# USB_HUB.net
KiCad netlist of a schematic drawn in Altium Designer
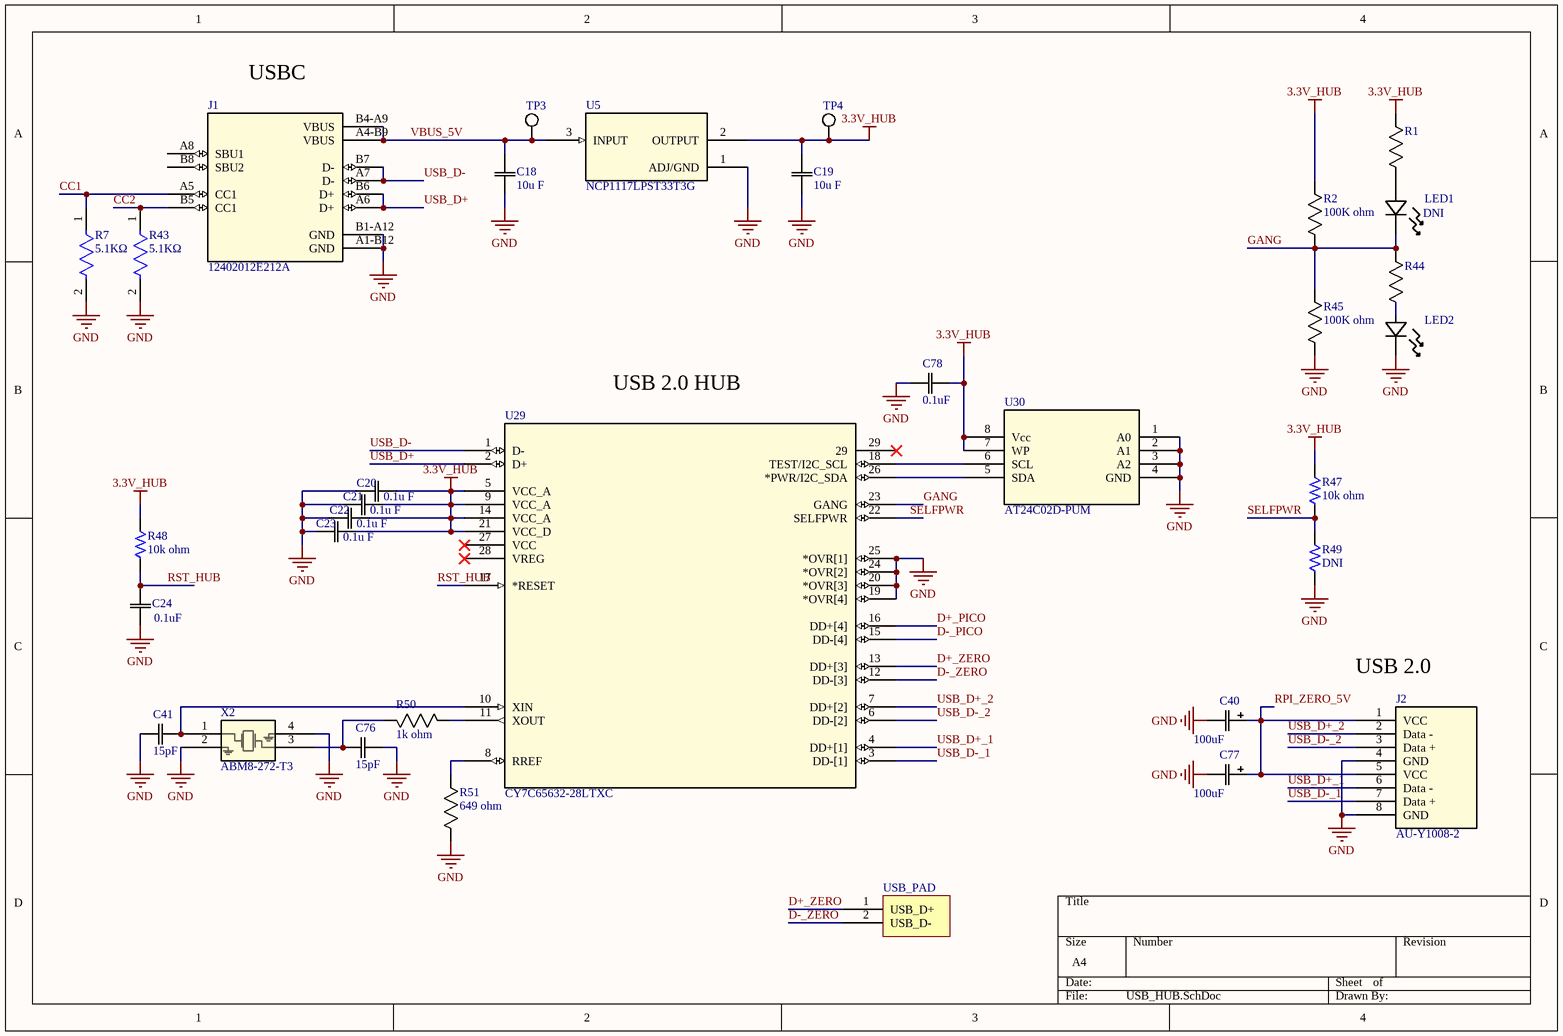
[diagram p0: USB_HUB.SchDoc]

(export (version "E")
  (design (tool "Eeschema 10.0.6"))
  (components
    (comp (ref "C18")
      (value "10u F")
      (footprint "G-21_MUR-M")
      (description "10 µF ±10% 16V Ceramic Capacitor X5R 0805 (2012 Metric)")
      (fields (field (name "Comment") "GRM21BR61C106KE15K"))
      (libsource (lib "Schlib1") (part "CAP_GRM21BR61C106KE15K"))
    )
    (comp (ref "C19")
      (value "10u F")
      (footprint "G-21_MUR-M")
      (description "10 µF ±10% 16V Ceramic Capacitor X5R 0805 (2012 Metric)")
      (fields (field (name "Comment") "GRM21BR61C106KE15K"))
      (libsource (lib "Schlib1") (part "CAP_GRM21BR61C106KE15K"))
    )
    (comp (ref "C20")
      (value "0.1u F")
      (footprint "CC0805N_YAG-M")
      (description "0.1 µF ±10% 50V Ceramic Capacitor X7R 0805 (2012 Metric)")
      (fields (field (name "Comment") "CC0805KRX7R9BB104"))
      (libsource (lib "Schlib1") (part "CAP_CC0805KRX7R9BB104"))
    )
    (comp (ref "C21")
      (value "0.1u F")
      (footprint "CC0805N_YAG-M")
      (description "0.1 µF ±10% 50V Ceramic Capacitor X7R 0805 (2012 Metric)")
      (fields (field (name "Comment") "CC0805KRX7R9BB104"))
      (libsource (lib "Schlib1") (part "CAP_CC0805KRX7R9BB104"))
    )
    (comp (ref "C22")
      (value "0.1u F")
      (footprint "CC0805N_YAG-M")
      (description "0.1 µF ±10% 50V Ceramic Capacitor X7R 0805 (2012 Metric)")
      (fields (field (name "Comment") "CC0805KRX7R9BB104"))
      (libsource (lib "Schlib1") (part "CAP_CC0805KRX7R9BB104"))
    )
    (comp (ref "C23")
      (value "0.1u F")
      (footprint "CC0805N_YAG-M")
      (description "0.1 µF ±10% 50V Ceramic Capacitor X7R 0805 (2012 Metric)")
      (fields (field (name "Comment") "CC0805KRX7R9BB104"))
      (libsource (lib "Schlib1") (part "CAP_CC0805KRX7R9BB104"))
    )
    (comp (ref "C24")
      (value "0.1uF")
      (footprint "CC0805N_YAG-M")
      (description "0.1 µF ±10% 50V Ceramic Capacitor X7R 0805 (2012 Metric)")
      (fields (field (name "Comment") "CC0805KRX7R9BB104"))
      (libsource (lib "Schlib1") (part "CAP_CC0805KRX7R9BB104"))
    )
    (comp (ref "C40")
      (value "100uF")
      (footprint "CAP_YX_6P3X11_RUB")
      (description "CAP ALUM 100UF 20% 35V RADIAL TH")
      (fields (field (name "Comment") "35YXJ100M6.3X11"))
      (libsource (lib "Schlib1") (part "CAP_35YXJ100M6.3X11"))
    )
    (comp (ref "C41")
      (value "15pF")
      (footprint "CAP_CC0805_YAG-M")
      (description "15 pF ±1% 50V Ceramic Capacitor C0G, NP0 0805 (2012 Metric)")
      (fields (field (name "Comment") "CC0805FRNPO9BN150"))
      (libsource (lib "Schlib1") (part "CAP_CC0805FRNPO9BN150"))
    )
    (comp (ref "C76")
      (value "15pF")
      (footprint "CAP_CC0805_YAG-M")
      (description "15 pF ±1% 50V Ceramic Capacitor C0G, NP0 0805 (2012 Metric)")
      (fields (field (name "Comment") "CC0805FRNPO9BN150"))
      (libsource (lib "Schlib1") (part "CAP_CC0805FRNPO9BN150"))
    )
    (comp (ref "C77")
      (value "100uF")
      (footprint "CAP_YX_6P3X11_RUB")
      (description "CAP ALUM 100UF 20% 35V RADIAL TH")
      (fields (field (name "Comment") "35YXJ100M6.3X11"))
      (libsource (lib "Schlib1") (part "CAP_35YXJ100M6.3X11"))
    )
    (comp (ref "C78")
      (value "0.1uF")
      (footprint "CC0805N_YAG-M")
      (description "0.1 µF ±10% 50V Ceramic Capacitor X7R 0805 (2012 Metric)")
      (fields (field (name "Comment") "CC0805KRX7R9BB104"))
      (libsource (lib "Schlib1") (part "CAP_CC0805KRX7R9BB104"))
    )
    (comp (ref "J1")
      (value "12402012E212A")
      (footprint "AMPHENOL_12402012E212A")
      (description "CONN RCP USB2.0 TYP C 24P SMD RA")
      (libsource (lib "Schlib1") (part "12402012E212A"))
    )
    (comp (ref "J2")
      (value "AU-Y1008-2")
      (footprint "CONN_AU-Y1008-2_ASM")
      (description "No Description Available")
      (libsource (lib "Schlib1") (part "AU-Y1008-2"))
    )
    (comp (ref "LED1")
      (value "B1931NG--20D001114U1930")
      (footprint "LED_B1931NG_HVK")
      (description "Green 525nm LED Indication - Discrete 3.3V 0603 (1608 Metric)")
      (fields (field (name "PARAMETER 1") "DNI"))
      (libsource (lib "Schlib1") (part "LED_B1931NG--20D001114U1930"))
    )
    (comp (ref "LED2")
      (value "B1931NG--20D001114U1930")
      (footprint "LED_B1931NG_HVK")
      (description "Green 525nm LED Indication - Discrete 3.3V 0603 (1608 Metric)")
      (libsource (lib "Schlib1") (part "LED_B1931NG--20D001114U1930"))
    )
    (comp (ref "R1")
      (value "RC0603FR-07169RL")
      (footprint "RC0603N_YAG-M")
      (description "169 Ohms ±1% 0.1W, 1/10W Chip Resistor 0603 (1608 Metric) Moisture Resistant Thick Film")
      (libsource (lib "Schlib1") (part "RES_RC0603FR-07169RL"))
    )
    (comp (ref "R2")
      (value "100K ohm")
      (footprint "RC0805N_YAG-M")
      (description "100 kOhms ±1% 0.125W, 1/8W Chip Resistor 0805 (2012 Metric) Moisture Resistant Thick Film")
      (fields (field (name "Comment") "RC0805FR-07100KL"))
      (libsource (lib "Schlib1") (part "RES_RC0805FR-07100KL"))
    )
    (comp (ref "R7")
      (value "RT0805FRE075K1L")
      (footprint "FP-RT0805-MFG")
      (description "RES SMD 5.1K OHM 1% 1/8W 0805")
      (fields
        (field (name "OCTOPART") "https://octopart.com/rt0805fre075k1l-yageo-1396245")
        (field (name "TOLERANCE") "0.0001")
        (field (name "RESISTANCE") "5.1KΩ")
      )
      (libsource (lib "Altium Content Vault") (part "1029c3af85768c4190bb7ad29bc67b5"))
    )
    (comp (ref "R43")
      (value "RT0805FRE075K1L")
      (footprint "FP-RT0805-MFG")
      (description "RES SMD 5.1K OHM 1% 1/8W 0805")
      (fields
        (field (name "OCTOPART") "https://octopart.com/rt0805fre075k1l-yageo-1396245")
        (field (name "TOLERANCE") "0.0001")
        (field (name "RESISTANCE") "5.1KΩ")
      )
      (libsource (lib "Altium Content Vault") (part "1029c3af85768c4190bb7ad29bc67b5"))
    )
    (comp (ref "R44")
      (value "RC0603FR-07169RL")
      (footprint "RC0603N_YAG-M")
      (description "169 Ohms ±1% 0.1W, 1/10W Chip Resistor 0603 (1608 Metric) Moisture Resistant Thick Film")
      (libsource (lib "Schlib1") (part "RES_RC0603FR-07169RL"))
    )
    (comp (ref "R45")
      (value "100K ohm")
      (footprint "RC0805N_YAG-M")
      (description "100 kOhms ±1% 0.125W, 1/8W Chip Resistor 0805 (2012 Metric) Moisture Resistant Thick Film")
      (fields (field (name "Comment") "RC0805FR-07100KL"))
      (libsource (lib "Schlib1") (part "RES_RC0805FR-07100KL"))
    )
    (comp (ref "R47")
      (value "10k ohm")
      (footprint "STA_RNCP0805_STP-M")
      (description "10 kOhms ±1% 0.25W, 1/4W Chip Resistor 0805 (2012 Metric) Anti-Sulfur Thin Film")
      (fields (field (name "Comment") "RNCP0805FTD10K0"))
      (libsource (lib "Schlib1") (part "RES_RNCP0805FTD10K0"))
    )
    (comp (ref "R48")
      (value "10k ohm")
      (footprint "STA_RNCP0805_STP-M")
      (description "10 kOhms ±1% 0.25W, 1/4W Chip Resistor 0805 (2012 Metric) Anti-Sulfur Thin Film")
      (fields (field (name "Comment") "RNCP0805FTD10K0"))
      (libsource (lib "Schlib1") (part "RES_RNCP0805FTD10K0"))
    )
    (comp (ref "R49")
      (value "DNI")
      (footprint "STA_RNCP0805_STP-M")
      (description "10 kOhms ±1% 0.25W, 1/4W Chip Resistor 0805 (2012 Metric) Anti-Sulfur Thin Film")
      (fields (field (name "Comment") "RNCP0805FTD10K0"))
      (libsource (lib "Schlib1") (part "RES_RNCP0805FTD10K0"))
    )
    (comp (ref "R50")
      (value "1k ohm")
      (footprint "RES_RNCF0805_STP-M")
      (description "1 kOhms ±0.5% 0.25W, 1/4W Chip Resistor 0805 (2012 Metric) Automotive AEC-Q200 Thin Film")
      (fields (field (name "Comment") "RNCF0805DTE1K00"))
      (libsource (lib "Schlib1") (part "RES_RNCF0805DTE1K00"))
    )
    (comp (ref "R51")
      (value "649 ohm")
      (footprint "RES_RNCF0805_STP-M")
      (description "649 mOhms ±1% 0.125W, 1/8W Chip Resistor 0805 (2012 Metric) Current Sense Thick Film")
      (fields (field (name "Comment") "RLC73K2AR649FTD"))
      (libsource (lib "Schlib1") (part "RES_RLC73K2AR649FTD"))
    )
    (comp (ref "TP3")
      (value "TestPoint")
      (footprint "Testpoint")
      (libsource (lib "Schlib1") (part "TestPoint"))
    )
    (comp (ref "TP4")
      (value "TestPoint")
      (footprint "Testpoint")
      (libsource (lib "Schlib1") (part "TestPoint"))
    )
    (comp (ref "U5")
      (value "NCP1117LPST33T3G")
      (footprint "SOT223-3_ONS-M")
      (description "Linear Voltage Regulator IC Positive Fixed 1 Output 1A SOT-223")
      (libsource (lib "Schlib1") (part "NCP1117LPST33T3G"))
    )
    (comp (ref "U29")
      (value "CY7C65632-28LTXC")
      (footprint "QFN-28-M")
      (description "USB Hub Controller USB 2.0 USB Interface 28-QFN (5x5)")
      (libsource (lib "Schlib1") (part "CY7C65632-28LTXC"))
    )
    (comp (ref "U30")
      (value "AT24C02D-PUM")
      (footprint "PDIP8_300MC_MCH")
      (description "IC EEPROM 2KBIT I2C 1MHZ 8DIP")
      (libsource (lib "Schlib1") (part "AT24C02D-PUM"))
    )
    (comp (ref "USB_PAD")
      (value "USB_PAD")
      (footprint "USB_PAD")
      (libsource (lib "Schlib1") (part "USB_PAD"))
    )
    (comp (ref "X2")
      (value "ABM8-272-T3")
      (footprint "ABM8-272-T3_ABR")
      (description "12 MHz ±30ppm Crystal 10pF 50 Ohms 4-SMD, No Lead")
      (libsource (lib "Schlib1") (part "ABM8-272-T3"))
    )
  )
  (nets
    (net (code "1") (name "/CC1") (class "Default")
      (node (ref "J1") (pin "A5") (pinfunction "CC1_A5") (pintype "bidirectional"))
      (node (ref "R7") (pin "1") (pinfunction "1_1") (pintype "passive"))
    )
    (net (code "2") (name "/CC2") (class "Default")
      (node (ref "J1") (pin "B5") (pinfunction "CC1_B5") (pintype "bidirectional"))
      (node (ref "R43") (pin "1") (pinfunction "1_1") (pintype "passive"))
    )
    (net (code "3") (name "/D+_PICO") (class "Default")
      (node (ref "U29") (pin "16") (pinfunction "DD+[4]_16") (pintype "bidirectional"))
    )
    (net (code "4") (name "/D+_ZERO") (class "Default")
      (node (ref "U29") (pin "13") (pinfunction "DD+[3]_13") (pintype "bidirectional"))
      (node (ref "USB_PAD") (pin "1") (pinfunction "USB_D+_1") (pintype "passive"))
    )
    (net (code "5") (name "/D-_PICO") (class "Default")
      (node (ref "U29") (pin "15") (pinfunction "DD-[4]_15") (pintype "bidirectional"))
    )
    (net (code "6") (name "/D-_ZERO") (class "Default")
      (node (ref "U29") (pin "12") (pinfunction "DD-[3]_12") (pintype "bidirectional"))
      (node (ref "USB_PAD") (pin "2") (pinfunction "USB_D-_2") (pintype "passive"))
    )
    (net (code "7") (name "/GANG") (class "Default")
      (node (ref "LED1") (pin "1") (pinfunction "CATHODE_1") (pintype "passive"))
      (node (ref "R2") (pin "1") (pinfunction "1_1") (pintype "passive"))
      (node (ref "R44") (pin "1") (pinfunction "1_1") (pintype "passive"))
      (node (ref "R45") (pin "2") (pinfunction "2_2") (pintype "passive"))
      (node (ref "U29") (pin "23") (pinfunction "GANG_23") (pintype "bidirectional"))
    )
    (net (code "8") (name "/RPI_ZERO_5V") (class "Default")
      (node (ref "C40") (pin "1") (pinfunction "1_1") (pintype "passive"))
      (node (ref "C77") (pin "1") (pinfunction "1_1") (pintype "passive"))
      (node (ref "J2") (pin "1") (pinfunction "VCC_1") (pintype "passive"))
      (node (ref "J2") (pin "5") (pinfunction "VCC_5") (pintype "passive"))
    )
    (net (code "9") (name "/RST_HUB") (class "Default")
      (node (ref "C24") (pin "2") (pinfunction "2_2") (pintype "passive"))
      (node (ref "R48") (pin "1") (pinfunction "1_1") (pintype "passive"))
      (node (ref "U29") (pin "17") (pinfunction "*RESET_17") (pintype "input"))
    )
    (net (code "10") (name "/SELFPWR") (class "Default")
      (node (ref "R47") (pin "1") (pinfunction "1_1") (pintype "passive"))
      (node (ref "R49") (pin "2") (pinfunction "2_2") (pintype "passive"))
      (node (ref "U29") (pin "22") (pinfunction "SELFPWR_22") (pintype "bidirectional"))
    )
    (net (code "11") (name "/USB_D+") (class "Default")
      (node (ref "J1") (pin "A6") (pinfunction "D+_A6") (pintype "bidirectional"))
      (node (ref "J1") (pin "B6") (pinfunction "D+_B6") (pintype "bidirectional"))
      (node (ref "U29") (pin "2") (pinfunction "D+_2") (pintype "bidirectional"))
    )
    (net (code "12") (name "/USB_D+_1") (class "Default")
      (node (ref "J2") (pin "6") (pinfunction "Data_-_6") (pintype "passive"))
      (node (ref "U29") (pin "4") (pinfunction "DD+[1]_4") (pintype "bidirectional"))
    )
    (net (code "13") (name "/USB_D+_2") (class "Default")
      (node (ref "J2") (pin "2") (pinfunction "Data_-_2") (pintype "passive"))
      (node (ref "U29") (pin "7") (pinfunction "DD+[2]_7") (pintype "bidirectional"))
    )
    (net (code "14") (name "/USB_D-") (class "Default")
      (node (ref "J1") (pin "A7") (pinfunction "D-_A7") (pintype "bidirectional"))
      (node (ref "J1") (pin "B7") (pinfunction "D-_B7") (pintype "bidirectional"))
      (node (ref "U29") (pin "1") (pinfunction "D-_1") (pintype "bidirectional"))
    )
    (net (code "15") (name "/USB_D-_1") (class "Default")
      (node (ref "J2") (pin "7") (pinfunction "Data_+_7") (pintype "passive"))
      (node (ref "U29") (pin "3") (pinfunction "DD-[1]_3") (pintype "bidirectional"))
    )
    (net (code "16") (name "/USB_D-_2") (class "Default")
      (node (ref "J2") (pin "3") (pinfunction "Data_+_3") (pintype "passive"))
      (node (ref "U29") (pin "6") (pinfunction "DD-[2]_6") (pintype "bidirectional"))
    )
    (net (code "17") (name "/VBUS_5V") (class "Default")
      (node (ref "C18") (pin "2") (pinfunction "2_2") (pintype "passive"))
      (node (ref "J1") (pin "A4-B9") (pinfunction "VBUS_A4-B9") (pintype "power_in"))
      (node (ref "J1") (pin "B4-A9") (pinfunction "VBUS_B4-A9") (pintype "power_in"))
      (node (ref "TP3") (pin "1") (pinfunction "1_1") (pintype "passive"))
      (node (ref "U5") (pin "3") (pinfunction "INPUT_3") (pintype "input"))
    )
    (net (code "18") (name "3.3V_HUB") (class "Default")
      (node (ref "C19") (pin "2") (pinfunction "2_2") (pintype "passive"))
      (node (ref "C20") (pin "1") (pinfunction "1_1") (pintype "passive"))
      (node (ref "C21") (pin "1") (pinfunction "1_1") (pintype "passive"))
      (node (ref "C22") (pin "1") (pinfunction "1_1") (pintype "passive"))
      (node (ref "C23") (pin "1") (pinfunction "1_1") (pintype "passive"))
      (node (ref "C78") (pin "1") (pinfunction "1_1") (pintype "passive"))
      (node (ref "R1") (pin "1") (pinfunction "1_1") (pintype "passive"))
      (node (ref "R2") (pin "2") (pinfunction "2_2") (pintype "passive"))
      (node (ref "R47") (pin "2") (pinfunction "2_2") (pintype "passive"))
      (node (ref "R48") (pin "2") (pinfunction "2_2") (pintype "passive"))
      (node (ref "TP4") (pin "1") (pinfunction "1_1") (pintype "passive"))
      (node (ref "U29") (pin "14") (pinfunction "VCC_A_14") (pintype "power_in"))
      (node (ref "U29") (pin "21") (pinfunction "VCC_D_21") (pintype "power_in"))
      (node (ref "U29") (pin "5") (pinfunction "VCC_A_5") (pintype "power_in"))
      (node (ref "U29") (pin "9") (pinfunction "VCC_A_9") (pintype "power_in"))
      (node (ref "U30") (pin "7") (pinfunction "WP_7") (pintype "passive"))
      (node (ref "U30") (pin "8") (pinfunction "Vcc_8") (pintype "power_in"))
      (node (ref "U5") (pin "2") (pinfunction "OUTPUT_2") (pintype "power_in"))
    )
    (net (code "19") (name "GND") (class "Default")
      (node (ref "C18") (pin "1") (pinfunction "1_1") (pintype "passive"))
      (node (ref "C19") (pin "1") (pinfunction "1_1") (pintype "passive"))
      (node (ref "C20") (pin "2") (pinfunction "2_2") (pintype "passive"))
      (node (ref "C21") (pin "2") (pinfunction "2_2") (pintype "passive"))
      (node (ref "C22") (pin "2") (pinfunction "2_2") (pintype "passive"))
      (node (ref "C23") (pin "2") (pinfunction "2_2") (pintype "passive"))
      (node (ref "C24") (pin "1") (pinfunction "1_1") (pintype "passive"))
      (node (ref "C40") (pin "2") (pinfunction "2_2") (pintype "passive"))
      (node (ref "C41") (pin "1") (pinfunction "1_1") (pintype "passive"))
      (node (ref "C76") (pin "2") (pinfunction "2_2") (pintype "passive"))
      (node (ref "C77") (pin "2") (pinfunction "2_2") (pintype "passive"))
      (node (ref "C78") (pin "2") (pinfunction "2_2") (pintype "passive"))
      (node (ref "J1") (pin "A1-B12") (pinfunction "GND_A1-B12") (pintype "power_in"))
      (node (ref "J1") (pin "B1-A12") (pinfunction "GND_B1-A12") (pintype "power_in"))
      (node (ref "J2") (pin "4") (pinfunction "GND_4") (pintype "passive"))
      (node (ref "J2") (pin "8") (pinfunction "GND_8") (pintype "passive"))
      (node (ref "LED2") (pin "1") (pinfunction "CATHODE_1") (pintype "passive"))
      (node (ref "R43") (pin "2") (pinfunction "2_2") (pintype "passive"))
      (node (ref "R45") (pin "1") (pinfunction "1_1") (pintype "passive"))
      (node (ref "R49") (pin "1") (pinfunction "1_1") (pintype "passive"))
      (node (ref "R51") (pin "1") (pinfunction "1_1") (pintype "passive"))
      (node (ref "R7") (pin "2") (pinfunction "2_2") (pintype "passive"))
      (node (ref "U29") (pin "19") (pinfunction "*OVR[4]_19") (pintype "bidirectional"))
      (node (ref "U29") (pin "20") (pinfunction "*OVR[3]_20") (pintype "bidirectional"))
      (node (ref "U29") (pin "24") (pinfunction "*OVR[2]_24") (pintype "bidirectional"))
      (node (ref "U29") (pin "25") (pinfunction "*OVR[1]_25") (pintype "bidirectional"))
      (node (ref "U30") (pin "1") (pinfunction "A0_1") (pintype "power_in"))
      (node (ref "U30") (pin "2") (pinfunction "A1_2") (pintype "power_in"))
      (node (ref "U30") (pin "3") (pinfunction "A2_3") (pintype "power_in"))
      (node (ref "U30") (pin "4") (pinfunction "GND_4") (pintype "power_in"))
      (node (ref "U5") (pin "1") (pinfunction "ADJ/GND_1") (pintype "power_in"))
      (node (ref "X2") (pin "2") (pinfunction "2_2") (pintype "passive"))
      (node (ref "X2") (pin "4") (pinfunction "4_4") (pintype "passive"))
    )
    (net (code "20") (name "Net-(C76-Pad1)") (class "Default")
      (node (ref "C76") (pin "1") (pinfunction "1_1") (pintype "passive"))
      (node (ref "R50") (pin "2") (pinfunction "2_2") (pintype "passive"))
      (node (ref "X2") (pin "3") (pinfunction "3_3") (pintype "passive"))
    )
    (net (code "21") (name "Net-(LED1-ANODE)") (class "Default")
      (node (ref "LED1") (pin "2") (pinfunction "ANODE_2") (pintype "passive"))
      (node (ref "R1") (pin "2") (pinfunction "2_2") (pintype "passive"))
    )
    (net (code "22") (name "Net-(LED2-ANODE)") (class "Default")
      (node (ref "LED2") (pin "2") (pinfunction "ANODE_2") (pintype "passive"))
      (node (ref "R44") (pin "2") (pinfunction "2_2") (pintype "passive"))
    )
    (net (code "23") (name "Net-(U29-*PWR{slash}I2C_SDA)") (class "Default")
      (node (ref "U29") (pin "26") (pinfunction "*PWR/I2C_SDA_26") (pintype "bidirectional"))
      (node (ref "U30") (pin "5") (pinfunction "SDA_5") (pintype "passive"))
    )
    (net (code "24") (name "Net-(U29-RREF)") (class "Default")
      (node (ref "R51") (pin "2") (pinfunction "2_2") (pintype "passive"))
      (node (ref "U29") (pin "8") (pinfunction "RREF_8") (pintype "bidirectional"))
    )
    (net (code "25") (name "Net-(U29-TEST{slash}I2C_SCL)") (class "Default")
      (node (ref "U29") (pin "18") (pinfunction "TEST/I2C_SCL_18") (pintype "bidirectional"))
      (node (ref "U30") (pin "6") (pinfunction "SCL_6") (pintype "passive"))
    )
    (net (code "26") (name "Net-(U29-XIN)") (class "Default")
      (node (ref "C41") (pin "2") (pinfunction "2_2") (pintype "passive"))
      (node (ref "U29") (pin "10") (pinfunction "XIN_10") (pintype "input"))
      (node (ref "X2") (pin "1") (pinfunction "1_1") (pintype "passive"))
    )
    (net (code "27") (name "Net-(U29-XOUT)") (class "Default")
      (node (ref "R50") (pin "1") (pinfunction "1_1") (pintype "passive"))
      (node (ref "U29") (pin "11") (pinfunction "XOUT_11") (pintype "output"))
    )
    (net (code "28") (name "unconnected-(J1-SBU1-PadA8)") (class "Default")
      (node (ref "J1") (pin "A8") (pinfunction "SBU1_A8") (pintype "bidirectional"))
    )
    (net (code "29") (name "unconnected-(J1-SBU2-PadB8)") (class "Default")
      (node (ref "J1") (pin "B8") (pinfunction "SBU2_B8") (pintype "bidirectional"))
    )
    (net (code "30") (name "unconnected-(U29-Pad29)") (class "Default")
      (node (ref "U29") (pin "29") (pinfunction "29_29") (pintype "passive+no_connect"))
    )
    (net (code "31") (name "unconnected-(U29-VCC-Pad27)") (class "Default")
      (node (ref "U29") (pin "27") (pinfunction "VCC_27") (pintype "power_in+no_connect"))
    )
    (net (code "32") (name "unconnected-(U29-VREG-Pad28)") (class "Default")
      (node (ref "U29") (pin "28") (pinfunction "VREG_28") (pintype "power_in+no_connect"))
    )
  )
)
